# WDT_TASTERI_M_S.net
KiCad netlist of a schematic drawn in Altium Designer
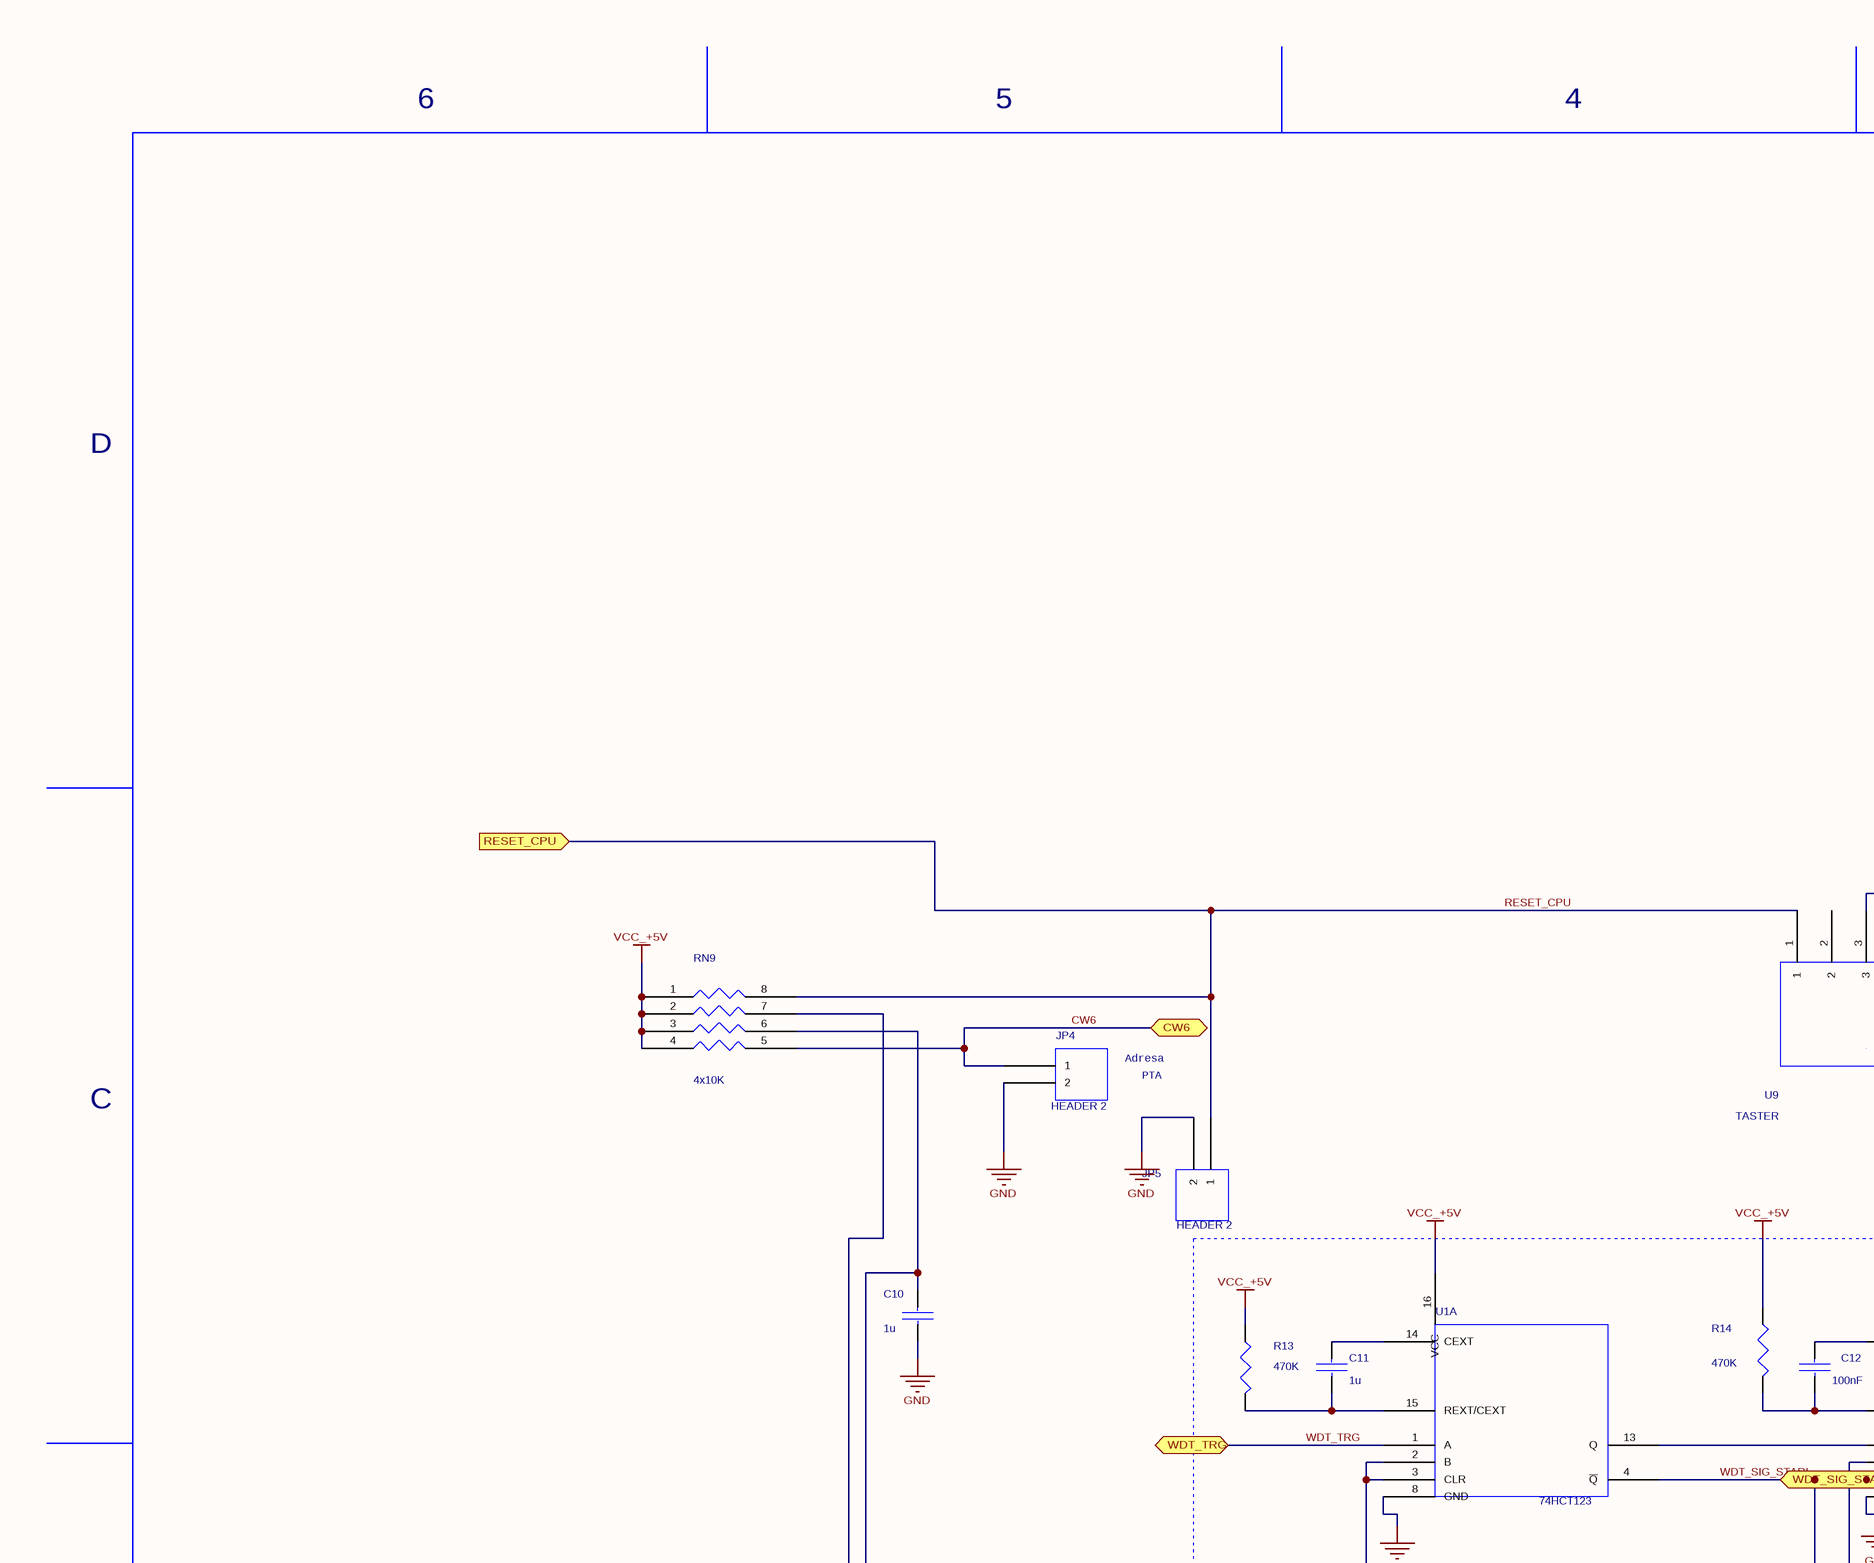
[diagram p0: WDT_TASTERI_M_S.SchDoc, top left]
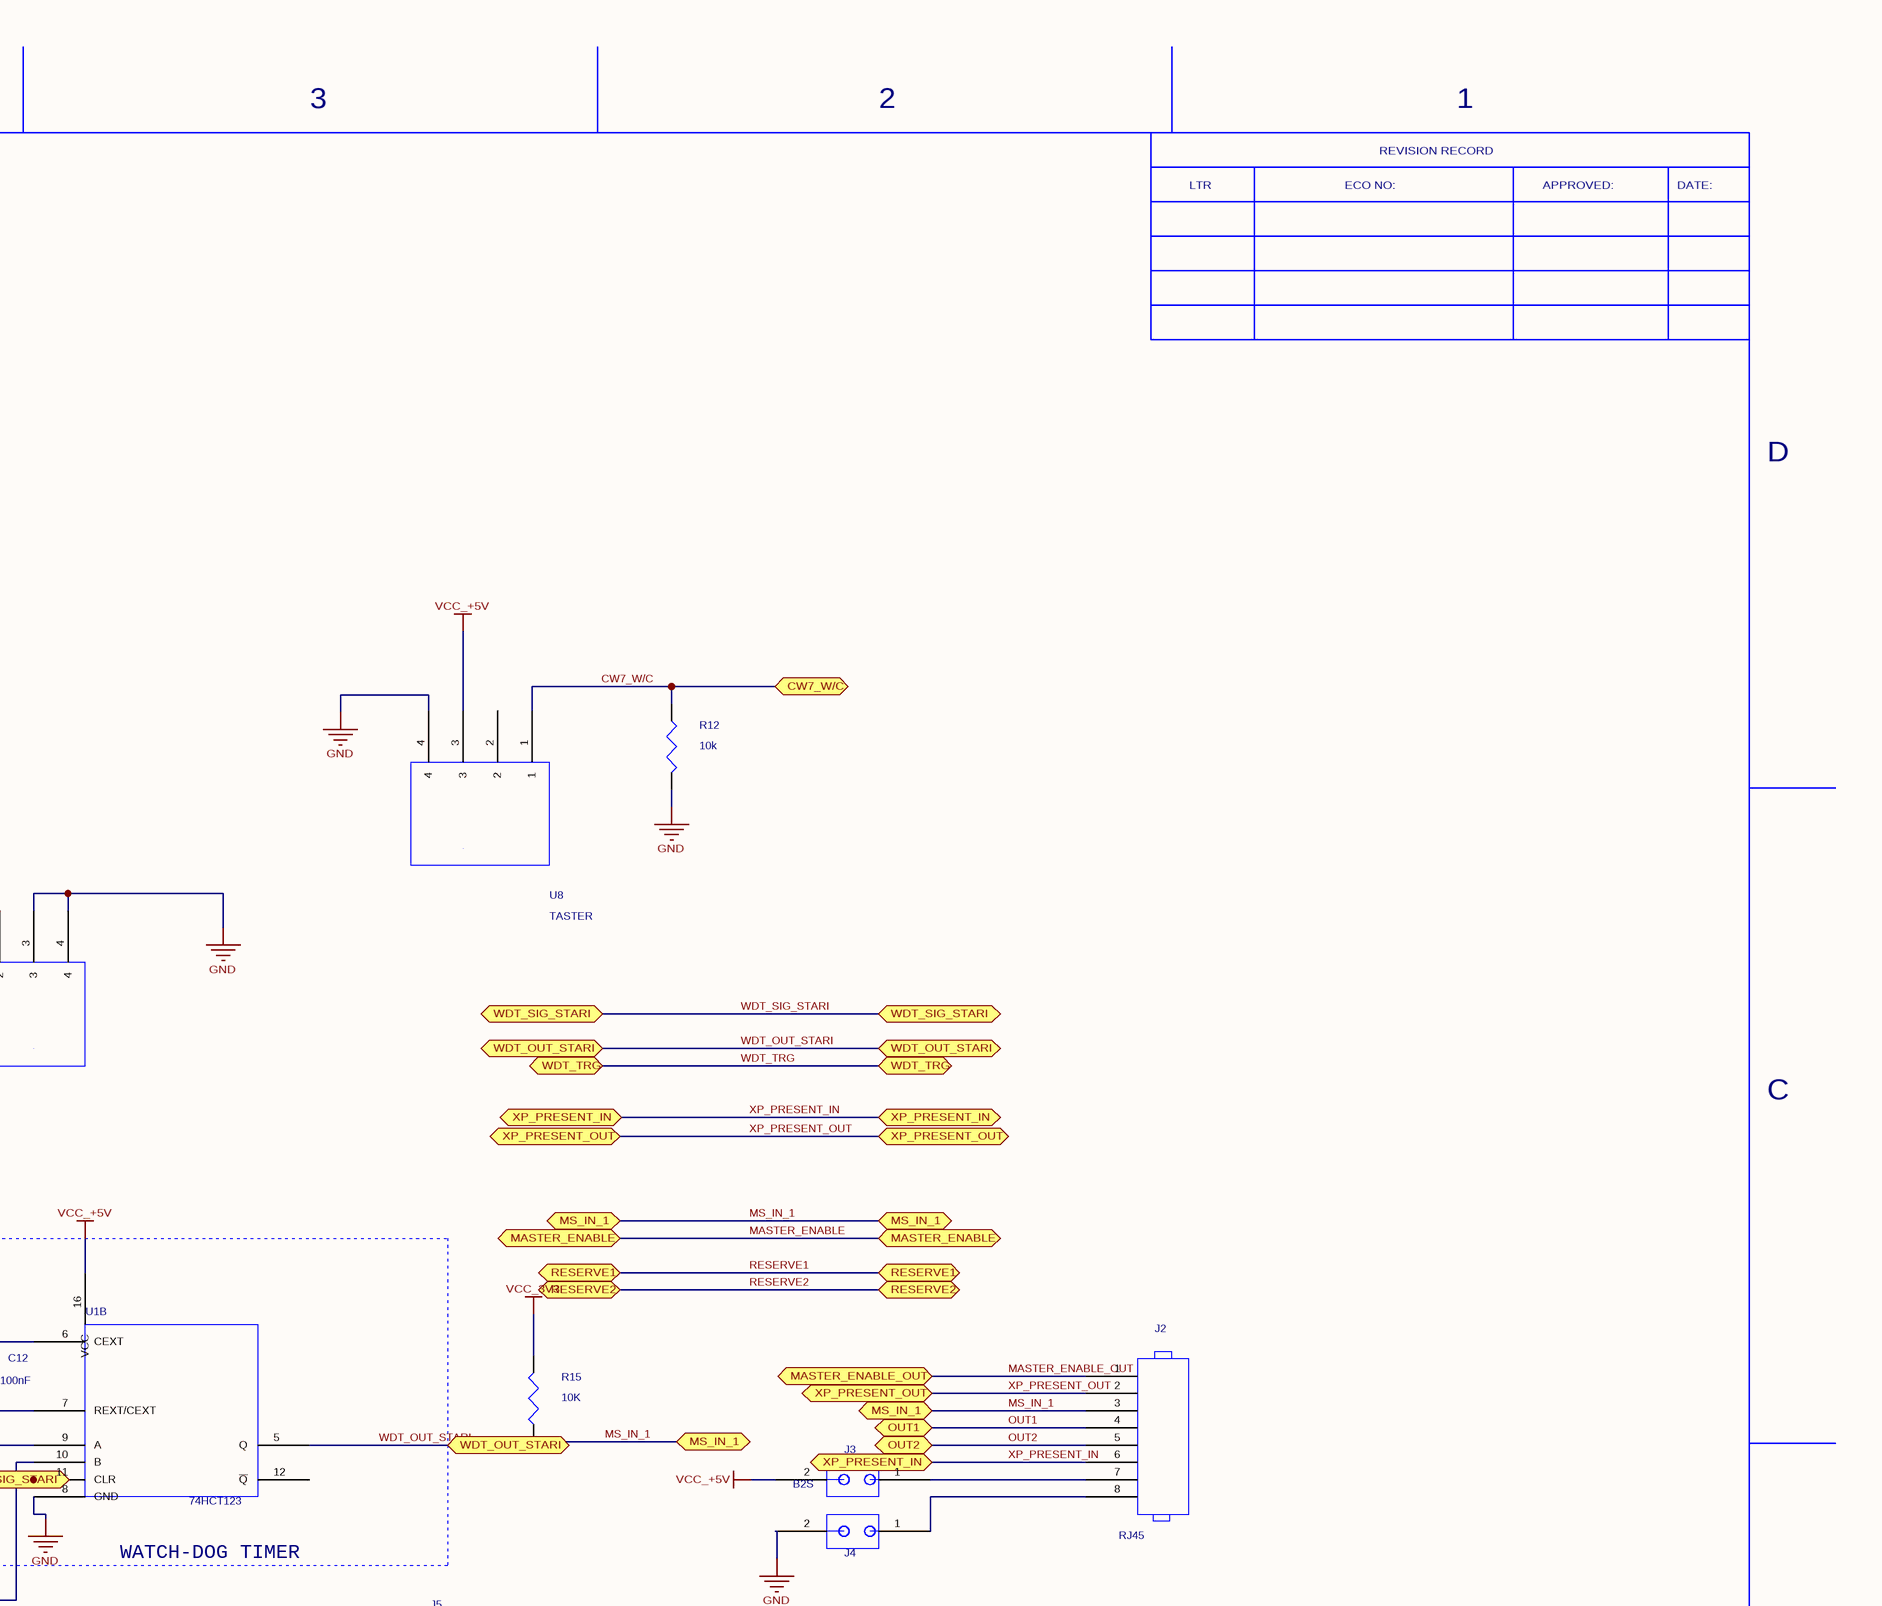
[diagram p1: WDT_TASTERI_M_S.SchDoc, top right]
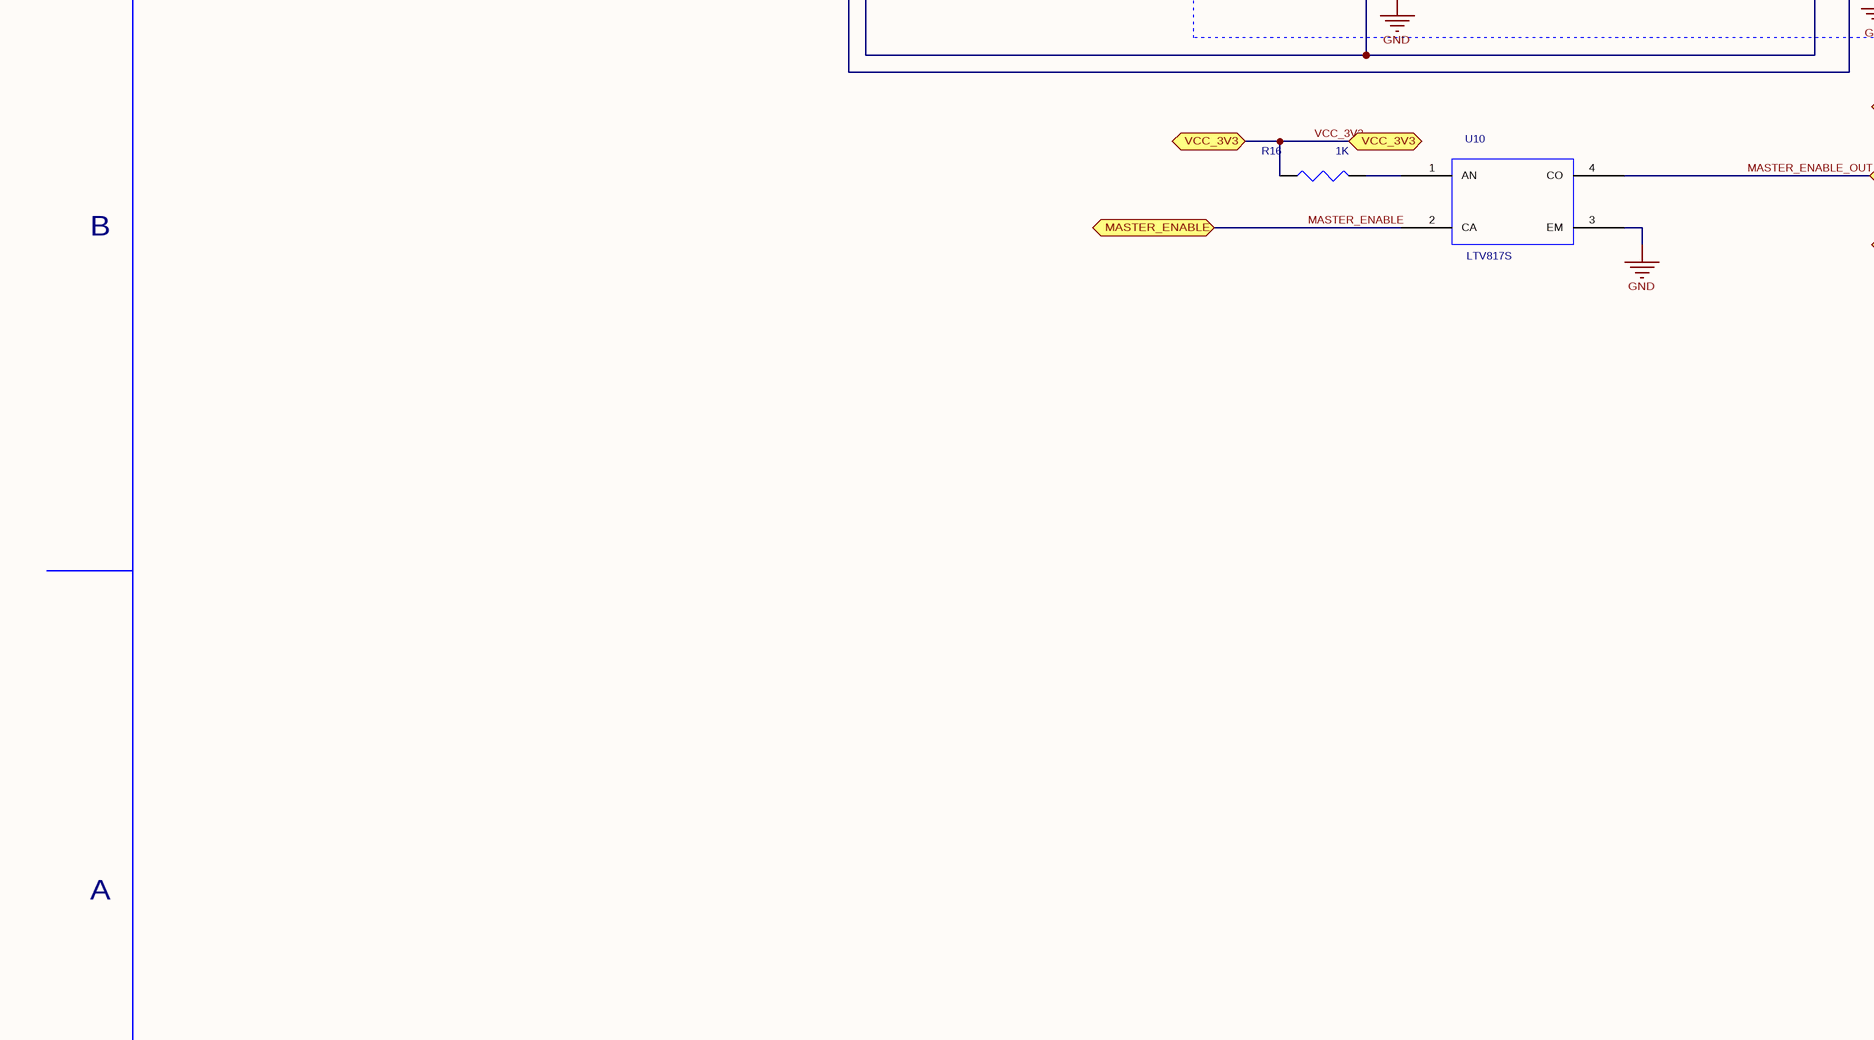
[diagram p2: WDT_TASTERI_M_S.SchDoc, bottom left]
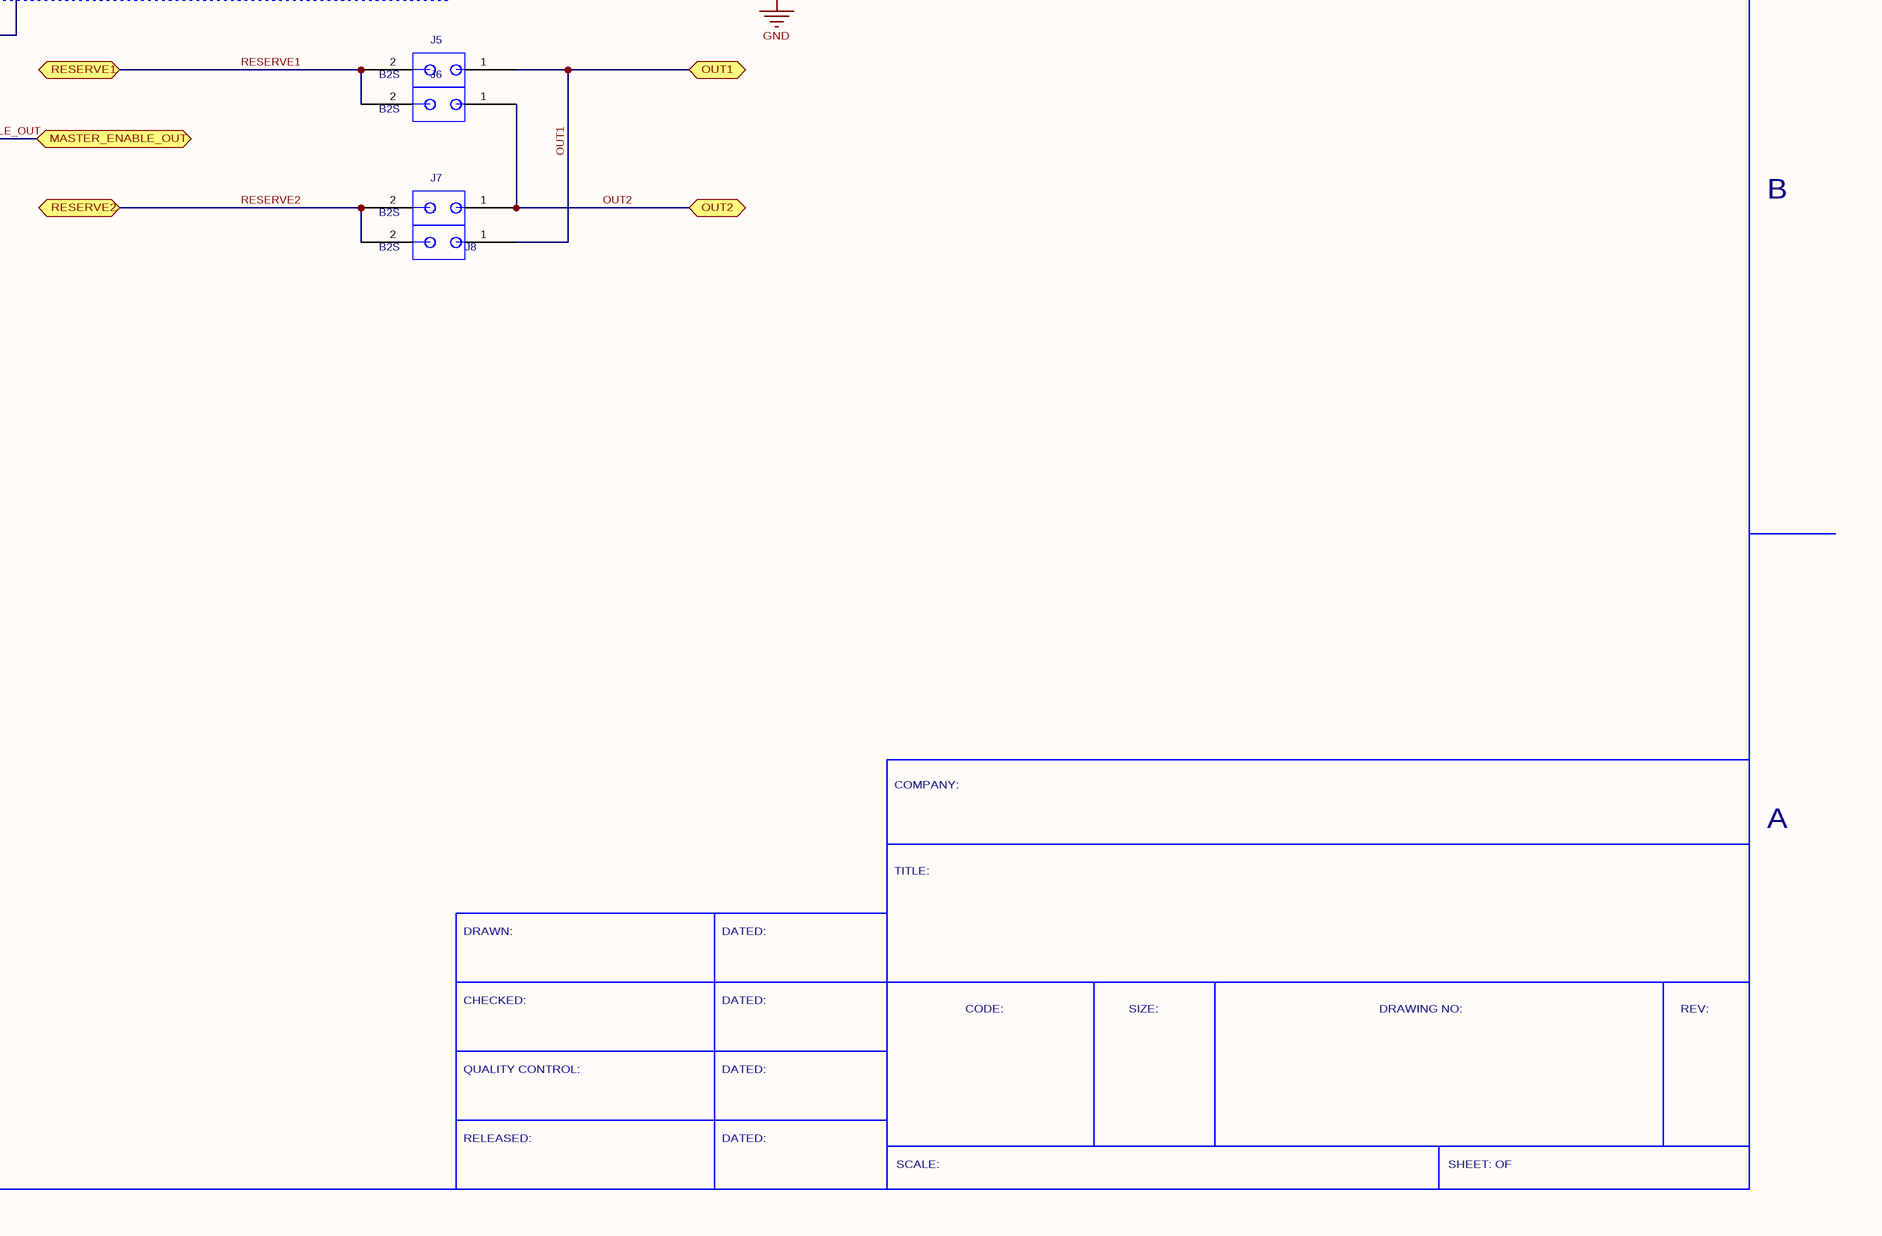
[diagram p3: WDT_TASTERI_M_S.SchDoc, bottom right]

(export (version "E")
  (design (tool "Eeschema 10.0.6"))
  (components
    (comp (ref "C10")
      (value "1u")
      (footprint "SM/C_0805")
      (fields (field (name "Comment") "C_2"))
      (libsource (lib "*") (part "C_2"))
    )
    (comp (ref "C11")
      (value "1u")
      (footprint "SM/C_0805")
      (fields (field (name "Comment") "C_2"))
      (libsource (lib "*") (part "C_2"))
    )
    (comp (ref "C12")
      (value "100nF")
      (footprint "SM/C_0805")
      (fields (field (name "Comment") "C_2"))
      (libsource (lib "*") (part "C_2"))
    )
    (comp (ref "J2")
      (value "RJ45")
      (footprint "TELE/TM.420FACE/8X8")
      (fields (field (name "Comment") "8_HEADER"))
      (libsource (lib "*") (part "8_HEADER"))
    )
    (comp (ref "J3")
      (value "B2S")
      (footprint "JUMPER_100")
      (fields (field (name "Comment") "B2S_0"))
      (libsource (lib "*") (part "B2S_0"))
    )
    (comp (ref "J4") (value "B2S_0") (footprint "JUMPER_100") (libsource (lib "*") (part "B2S_0")))
    (comp (ref "J5")
      (value "B2S")
      (footprint "JUMPER_100")
      (fields (field (name "Comment") "B2S_0"))
      (libsource (lib "*") (part "B2S_0"))
    )
    (comp (ref "J6")
      (value "B2S")
      (footprint "JUMPER_100")
      (fields (field (name "Comment") "B2S_0"))
      (libsource (lib "*") (part "B2S_0"))
    )
    (comp (ref "J7")
      (value "B2S")
      (footprint "JUMPER_100")
      (fields (field (name "Comment") "B2S_0"))
      (libsource (lib "*") (part "B2S_0"))
    )
    (comp (ref "J8")
      (value "B2S")
      (footprint "JUMPER_100")
      (fields (field (name "Comment") "B2S_0"))
      (libsource (lib "*") (part "B2S_0"))
    )
    (comp (ref "JP4")
      (value "HEADER 2")
      (footprint "JUMPER_100")
      (fields (field (name "Comment") "HEADER_2"))
      (libsource (lib "*") (part "HEADER_2"))
    )
    (comp (ref "JP5")
      (value "HEADER 2")
      (footprint "JUMPER_100")
      (fields (field (name "Comment") "HEADER_2"))
      (libsource (lib "*") (part "HEADER_2"))
    )
    (comp (ref "R12")
      (value "10k")
      (footprint "SM/R_1206")
      (fields (field (name "Comment") "RESISTOR_2"))
      (libsource (lib "*") (part "RESISTOR_2"))
    )
    (comp (ref "R13")
      (value "470K")
      (footprint "SM/R_1206")
      (fields (field (name "Comment") "RESISTOR_2"))
      (libsource (lib "*") (part "RESISTOR_2"))
    )
    (comp (ref "R14")
      (value "470K")
      (footprint "SM/R_1206")
      (fields (field (name "Comment") "RESISTOR_2"))
      (libsource (lib "*") (part "RESISTOR_2"))
    )
    (comp (ref "R15")
      (value "10K")
      (footprint "SM/R_1206")
      (fields (field (name "Comment") "RESISTOR_2"))
      (libsource (lib "*") (part "RESISTOR_2"))
    )
    (comp (ref "R16")
      (value "1K")
      (footprint "SM/R_1206")
      (fields (field (name "Comment") "RESISTOR_2"))
      (libsource (lib "*") (part "RESISTOR_2"))
    )
    (comp (ref "RN9")
      (value "4x10K")
      (footprint "SMD_RX4")
      (fields (field (name "Comment") "RESAR_IS_4/SM"))
      (libsource (lib "*") (part "RESAR_IS_4/SM"))
    )
    (comp (ref "U1")
      (value "74HCT123")
      (footprint "SOG.050/16/WG.244/L.375")
      (fields (field (name "Comment") "74HCT123_1"))
      (libsource (lib "*") (part "74HCT123_1"))
    )
    (comp (ref "U8")
      (value "TASTER")
      (footprint "TP33WW080-SPST_PADS")
      (description "CW_TASTER")
      (fields (field (name "Comment") "SWITCH_BOJKE"))
      (libsource (lib "*") (part "SWITCH_BOJKE"))
    )
    (comp (ref "U9")
      (value "TASTER")
      (footprint "TP33WW080-SPST_PADS")
      (description "RST_TASTER")
      (fields (field (name "Comment") "SWITCH_BOJKE"))
      (libsource (lib "*") (part "SWITCH_BOJKE"))
    )
    (comp (ref "U10")
      (value "LTV817S")
      (footprint "LTV814S")
      (fields (field (name "Comment") "LTV-817"))
      (libsource (lib "*") (part "LTV-817"))
    )
  )
  (nets
    (net (code "1") (name "/CW6") (class "Default")
      (node (ref "JP4") (pin "1") (pinfunction "1_1") (pintype "passive"))
      (node (ref "RN9") (pin "5") (pinfunction "5_5") (pintype "passive"))
    )
    (net (code "2") (name "/CW7_W{slash}C") (class "Default")
      (node (ref "R12") (pin "1") (pinfunction "1_1") (pintype "passive"))
      (node (ref "U8") (pin "1") (pinfunction "1_1") (pintype "passive"))
    )
    (net (code "3") (name "/MASTER_ENABLE") (class "Default")
      (node (ref "U10") (pin "2") (pinfunction "CA_2") (pintype "passive"))
    )
    (net (code "4") (name "/MASTER_ENABLE_OUT") (class "Default")
      (node (ref "J2") (pin "1") (pinfunction "1_1") (pintype "passive"))
      (node (ref "U10") (pin "4") (pinfunction "CO_4") (pintype "passive"))
    )
    (net (code "5") (name "/MS_IN_1") (class "Default")
      (node (ref "J2") (pin "3") (pinfunction "3_3") (pintype "passive"))
      (node (ref "R15") (pin "1") (pinfunction "1_1") (pintype "passive"))
    )
    (net (code "6") (name "/OUT1") (class "Default")
      (node (ref "J2") (pin "4") (pinfunction "4_4") (pintype "passive"))
      (node (ref "J5") (pin "1") (pinfunction "1_1") (pintype "passive"))
      (node (ref "J8") (pin "1") (pinfunction "1_1") (pintype "passive"))
    )
    (net (code "7") (name "/OUT2") (class "Default")
      (node (ref "J2") (pin "5") (pinfunction "5_5") (pintype "passive"))
      (node (ref "J6") (pin "1") (pinfunction "1_1") (pintype "passive"))
      (node (ref "J7") (pin "1") (pinfunction "1_1") (pintype "passive"))
    )
    (net (code "8") (name "/RESERVE1") (class "Default")
      (node (ref "J5") (pin "2") (pinfunction "2_2") (pintype "passive"))
      (node (ref "J6") (pin "2") (pinfunction "2_2") (pintype "passive"))
    )
    (net (code "9") (name "/RESERVE2") (class "Default")
      (node (ref "J7") (pin "2") (pinfunction "2_2") (pintype "passive"))
      (node (ref "J8") (pin "2") (pinfunction "2_2") (pintype "passive"))
    )
    (net (code "10") (name "/RESET_CPU") (class "Default")
      (node (ref "JP5") (pin "1") (pinfunction "1_1") (pintype "passive"))
      (node (ref "RN9") (pin "8") (pinfunction "8_8") (pintype "passive"))
      (node (ref "U9") (pin "1") (pinfunction "1_1") (pintype "passive"))
    )
    (net (code "11") (name "/WDT_OUT_STARI") (class "Default")
      (node (ref "U1") (pin "5") (pinfunction "Q_5") (pintype "passive"))
    )
    (net (code "12") (name "/WDT_SIG_STARI") (class "Default")
      (node (ref "U1") (pin "4") (pinfunction "Q_4") (pintype "passive"))
    )
    (net (code "13") (name "/WDT_TRG") (class "Default")
      (node (ref "U1") (pin "1") (pinfunction "A_1") (pintype "passive"))
    )
    (net (code "14") (name "/XP_PRESENT_IN") (class "Default")
      (node (ref "J2") (pin "6") (pinfunction "6_6") (pintype "passive"))
    )
    (net (code "15") (name "/XP_PRESENT_OUT") (class "Default")
      (node (ref "J2") (pin "2") (pinfunction "2_2") (pintype "passive"))
    )
    (net (code "16") (name "GND") (class "Default")
      (node (ref "C10") (pin "2") (pinfunction "2_2") (pintype "passive"))
      (node (ref "J4") (pin "2") (pinfunction "2_2") (pintype "passive"))
      (node (ref "JP4") (pin "2") (pinfunction "2_2") (pintype "passive"))
      (node (ref "JP5") (pin "2") (pinfunction "2_2") (pintype "passive"))
      (node (ref "R12") (pin "2") (pinfunction "2_2") (pintype "passive"))
      (node (ref "U1") (pin "8") (pinfunction "GND_8") (pintype "power_in"))
      (node (ref "U10") (pin "3") (pinfunction "EM_3") (pintype "passive"))
      (node (ref "U8") (pin "4") (pinfunction "4_4") (pintype "passive"))
      (node (ref "U9") (pin "3") (pinfunction "3_3") (pintype "passive"))
      (node (ref "U9") (pin "4") (pinfunction "4_4") (pintype "passive"))
    )
    (net (code "17") (name "Net-(J2-Pad7)") (class "Default")
      (node (ref "J2") (pin "7") (pinfunction "7_7") (pintype "passive"))
      (node (ref "J3") (pin "1") (pinfunction "1_1") (pintype "passive"))
    )
    (net (code "18") (name "Net-(J2-Pad8)") (class "Default")
      (node (ref "J2") (pin "8") (pinfunction "8_8") (pintype "passive"))
      (node (ref "J4") (pin "1") (pinfunction "1_1") (pintype "passive"))
    )
    (net (code "19") (name "Net-(U1A-B)") (class "Default")
      (node (ref "C10") (pin "1") (pinfunction "1_1") (pintype "passive"))
      (node (ref "RN9") (pin "6") (pinfunction "6_6") (pintype "passive"))
      (node (ref "U1") (pin "11") (pinfunction "CLR_11") (pintype "passive"))
      (node (ref "U1") (pin "2") (pinfunction "B_2") (pintype "passive"))
      (node (ref "U1") (pin "3") (pinfunction "CLR_3") (pintype "passive"))
    )
    (net (code "20") (name "Net-(U1A-CEXT)") (class "Default")
      (node (ref "C11") (pin "1") (pinfunction "1_1") (pintype "passive"))
      (node (ref "U1") (pin "14") (pinfunction "CEXT_14") (pintype "passive"))
    )
    (net (code "21") (name "Net-(U1A-REXT{slash}CEXT)") (class "Default")
      (node (ref "C11") (pin "2") (pinfunction "2_2") (pintype "passive"))
      (node (ref "R13") (pin "2") (pinfunction "2_2") (pintype "passive"))
      (node (ref "U1") (pin "15") (pinfunction "REXT/CEXT_15") (pintype "passive"))
    )
    (net (code "22") (name "Net-(U1B-A)") (class "Default")
      (node (ref "U1") (pin "13") (pinfunction "Q_13") (pintype "passive"))
      (node (ref "U1") (pin "9") (pinfunction "A_9") (pintype "passive"))
    )
    (net (code "23") (name "Net-(U1B-B)") (class "Default")
      (node (ref "RN9") (pin "7") (pinfunction "7_7") (pintype "passive"))
      (node (ref "U1") (pin "10") (pinfunction "B_10") (pintype "passive"))
    )
    (net (code "24") (name "Net-(U1B-CEXT)") (class "Default")
      (node (ref "C12") (pin "1") (pinfunction "1_1") (pintype "passive"))
      (node (ref "U1") (pin "6") (pinfunction "CEXT_6") (pintype "passive"))
    )
    (net (code "25") (name "Net-(U1B-REXT{slash}CEXT)") (class "Default")
      (node (ref "C12") (pin "2") (pinfunction "2_2") (pintype "passive"))
      (node (ref "R14") (pin "2") (pinfunction "2_2") (pintype "passive"))
      (node (ref "U1") (pin "7") (pinfunction "REXT/CEXT_7") (pintype "passive"))
    )
    (net (code "26") (name "Net-(U10-AN)") (class "Default")
      (node (ref "R16") (pin "2") (pinfunction "2_2") (pintype "passive"))
      (node (ref "U10") (pin "1") (pinfunction "AN_1") (pintype "passive"))
    )
    (net (code "27") (name "VCC_+5V") (class "Default")
      (node (ref "J3") (pin "2") (pinfunction "2_2") (pintype "passive"))
      (node (ref "R13") (pin "1") (pinfunction "1_1") (pintype "passive"))
      (node (ref "R14") (pin "1") (pinfunction "1_1") (pintype "passive"))
      (node (ref "RN9") (pin "1") (pinfunction "1_1") (pintype "passive"))
      (node (ref "RN9") (pin "2") (pinfunction "2_2") (pintype "passive"))
      (node (ref "RN9") (pin "3") (pinfunction "3_3") (pintype "passive"))
      (node (ref "RN9") (pin "4") (pinfunction "4_4") (pintype "passive"))
      (node (ref "U1") (pin "16") (pinfunction "VCC_16") (pintype "power_in"))
      (node (ref "U8") (pin "3") (pinfunction "3_3") (pintype "passive"))
    )
    (net (code "28") (name "VCC_3V3") (class "Default")
      (node (ref "R15") (pin "2") (pinfunction "2_2") (pintype "passive"))
      (node (ref "R16") (pin "1") (pinfunction "1_1") (pintype "passive"))
    )
    (net (code "29") (name "unconnected-(U1B-Q-Pad12)") (class "Default")
      (node (ref "U1") (pin "12") (pinfunction "Q_12") (pintype "passive"))
    )
    (net (code "30") (name "unconnected-(U8-Pad2)") (class "Default")
      (node (ref "U8") (pin "2") (pinfunction "2_2") (pintype "passive"))
    )
    (net (code "31") (name "unconnected-(U9-Pad2)") (class "Default")
      (node (ref "U9") (pin "2") (pinfunction "2_2") (pintype "passive"))
    )
  )
)
